# LinSen_beta.net
KiCad netlist of a schematic drawn in EAGLE
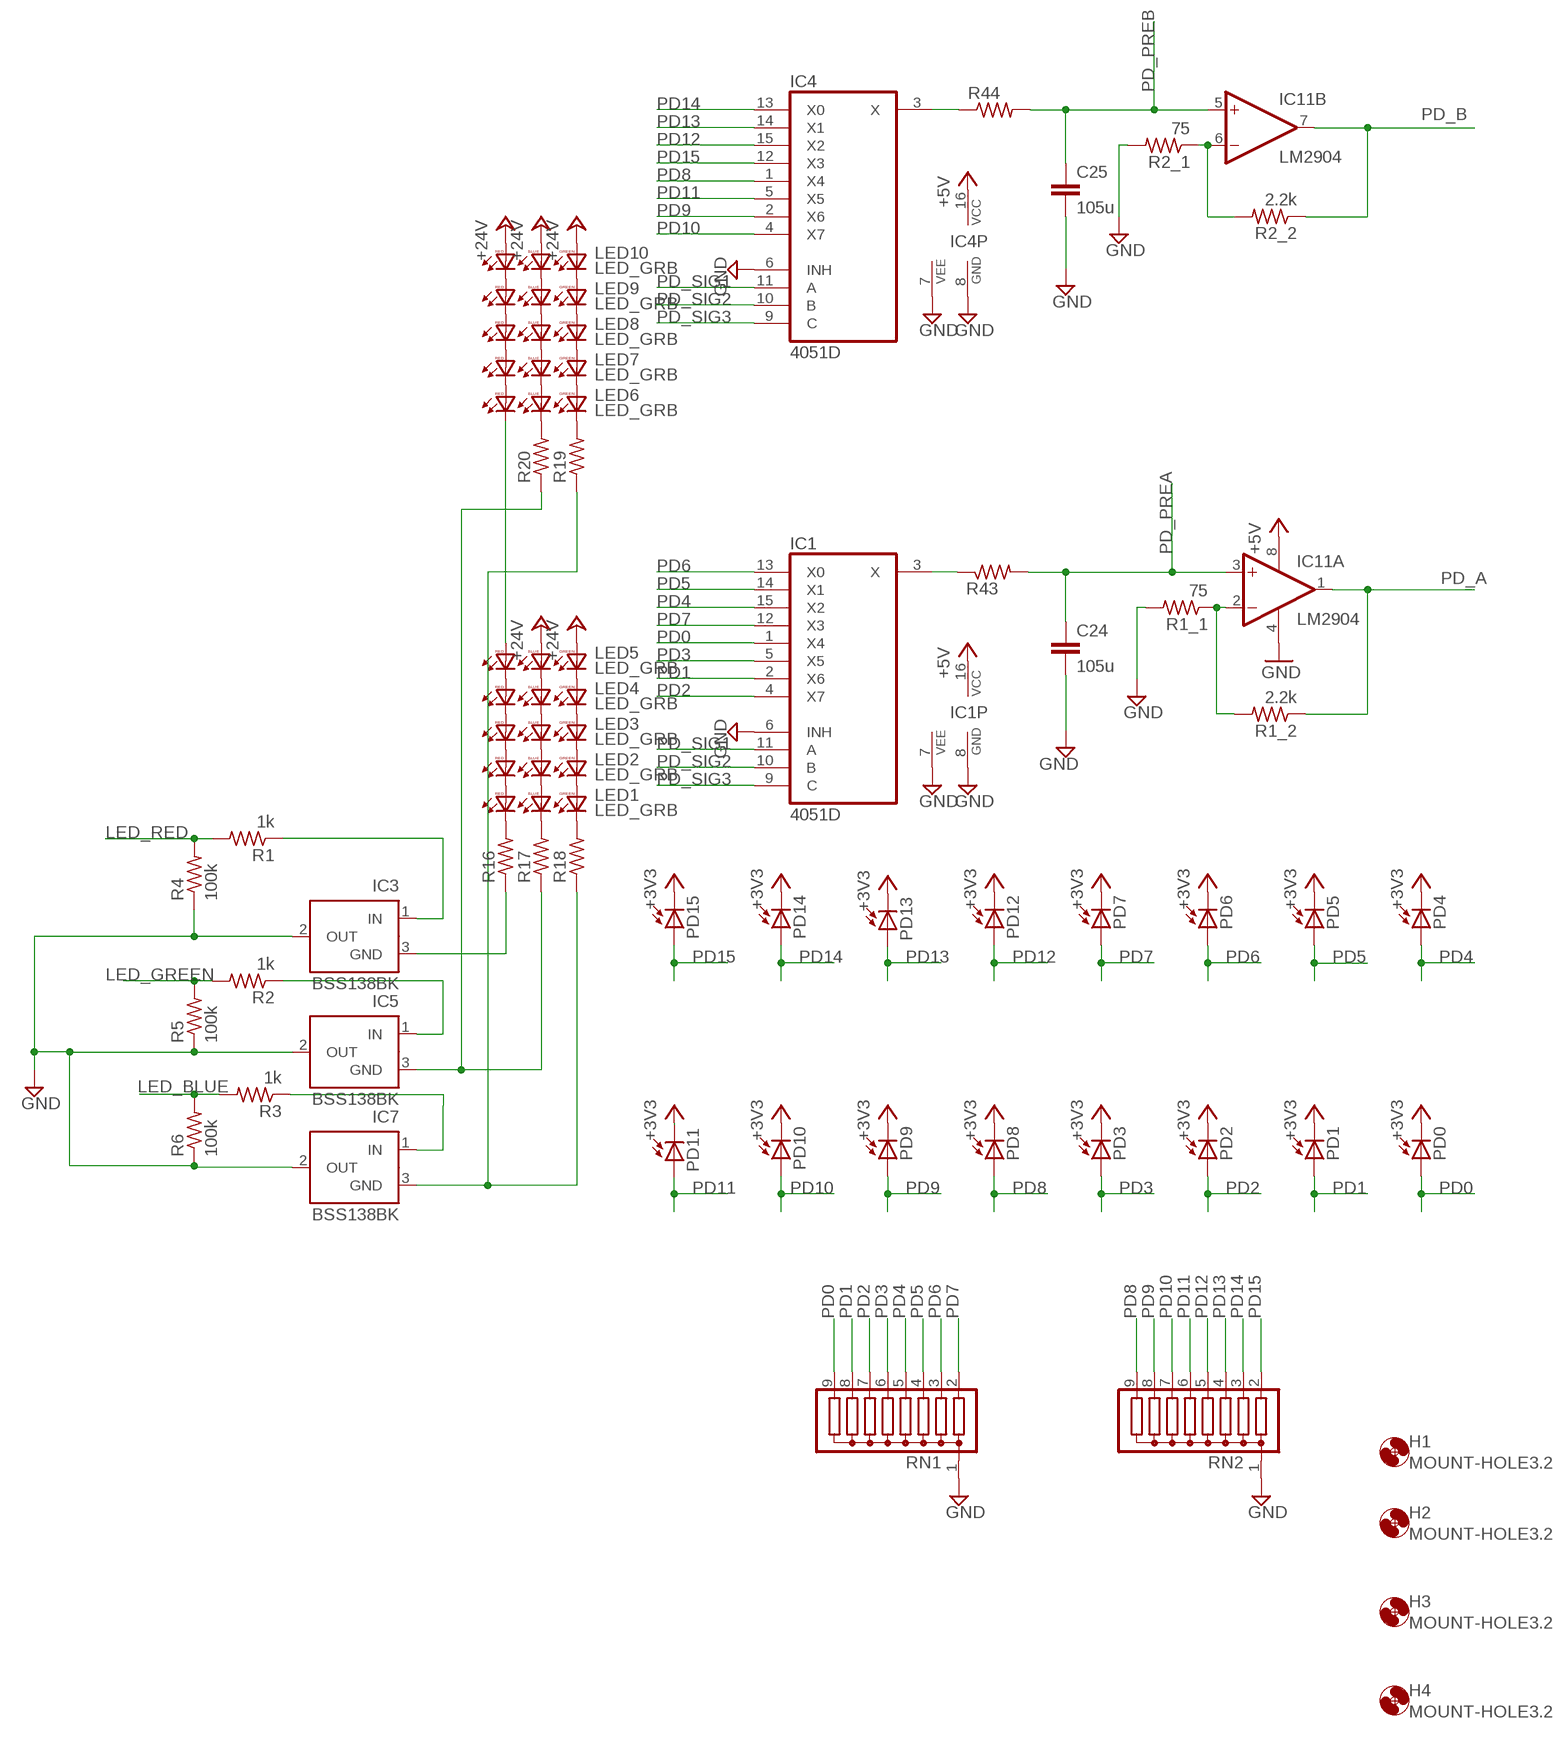
[diagram p0: schematic, sheet 1]
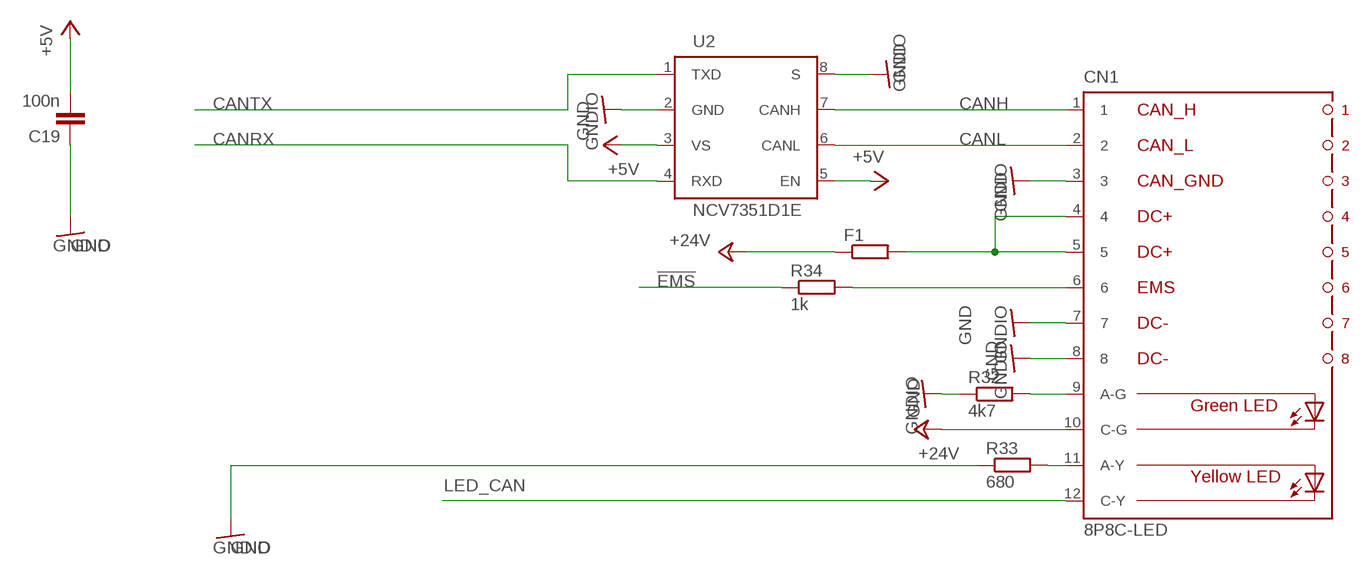
[diagram p1: schematic, sheet 2]
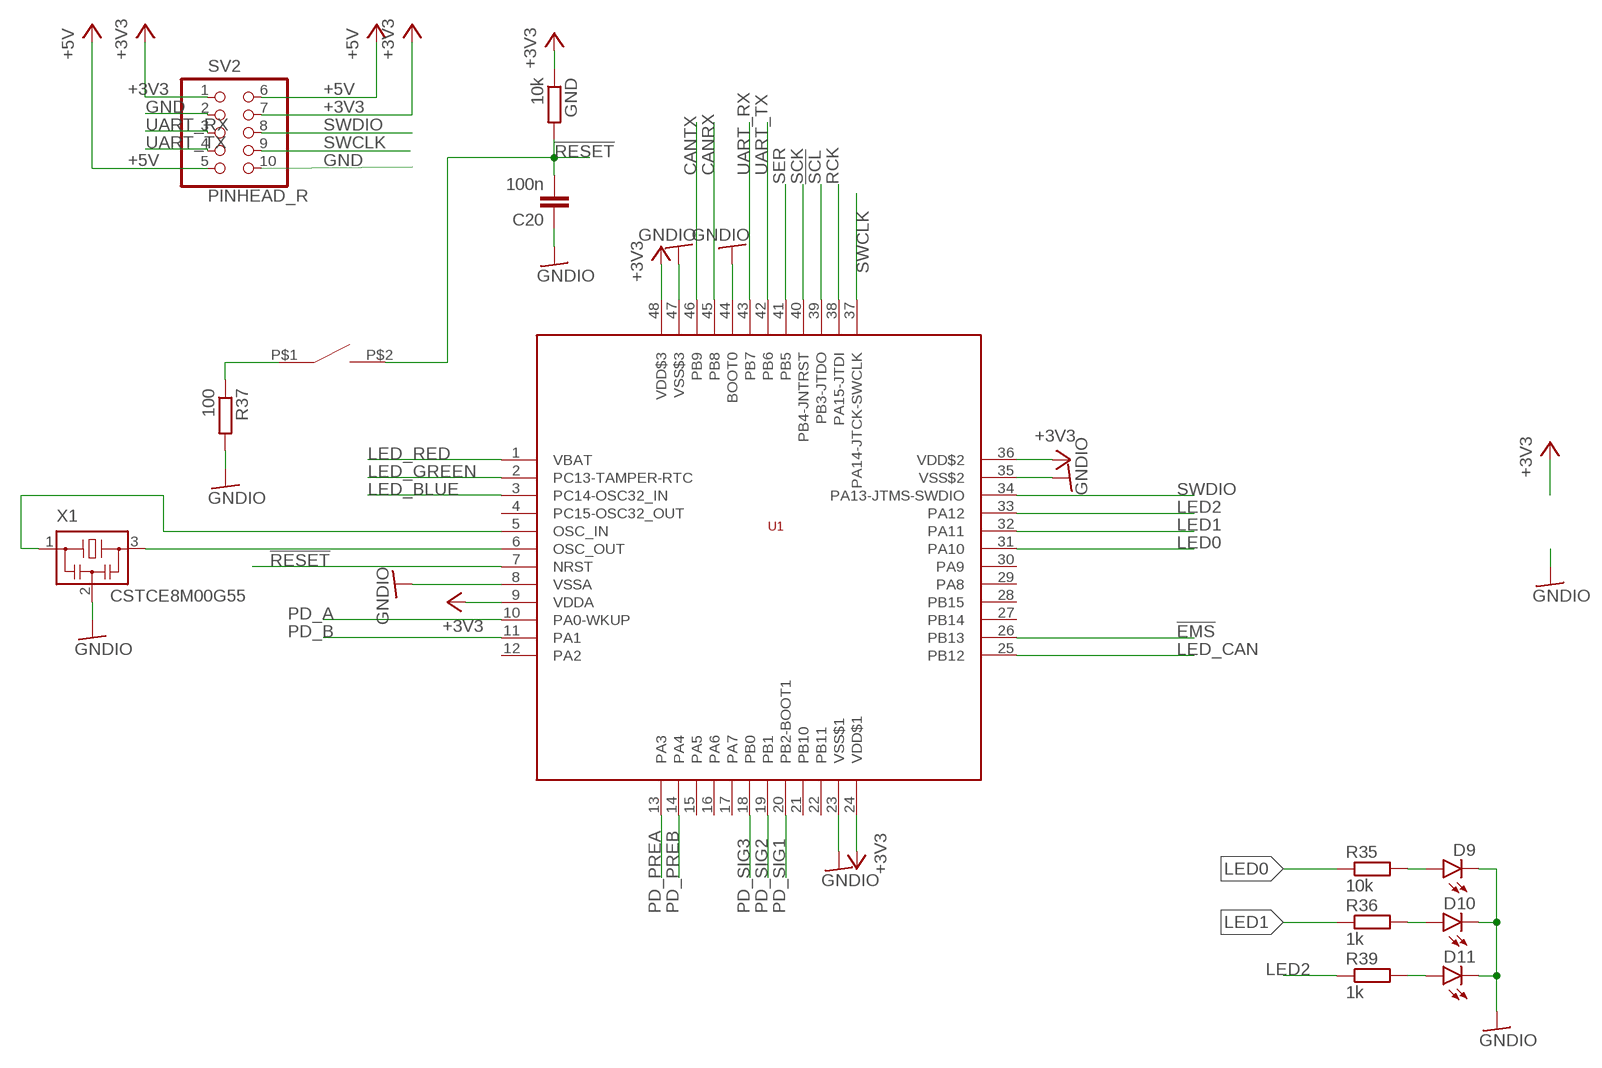
[diagram p2: schematic, sheet 3]
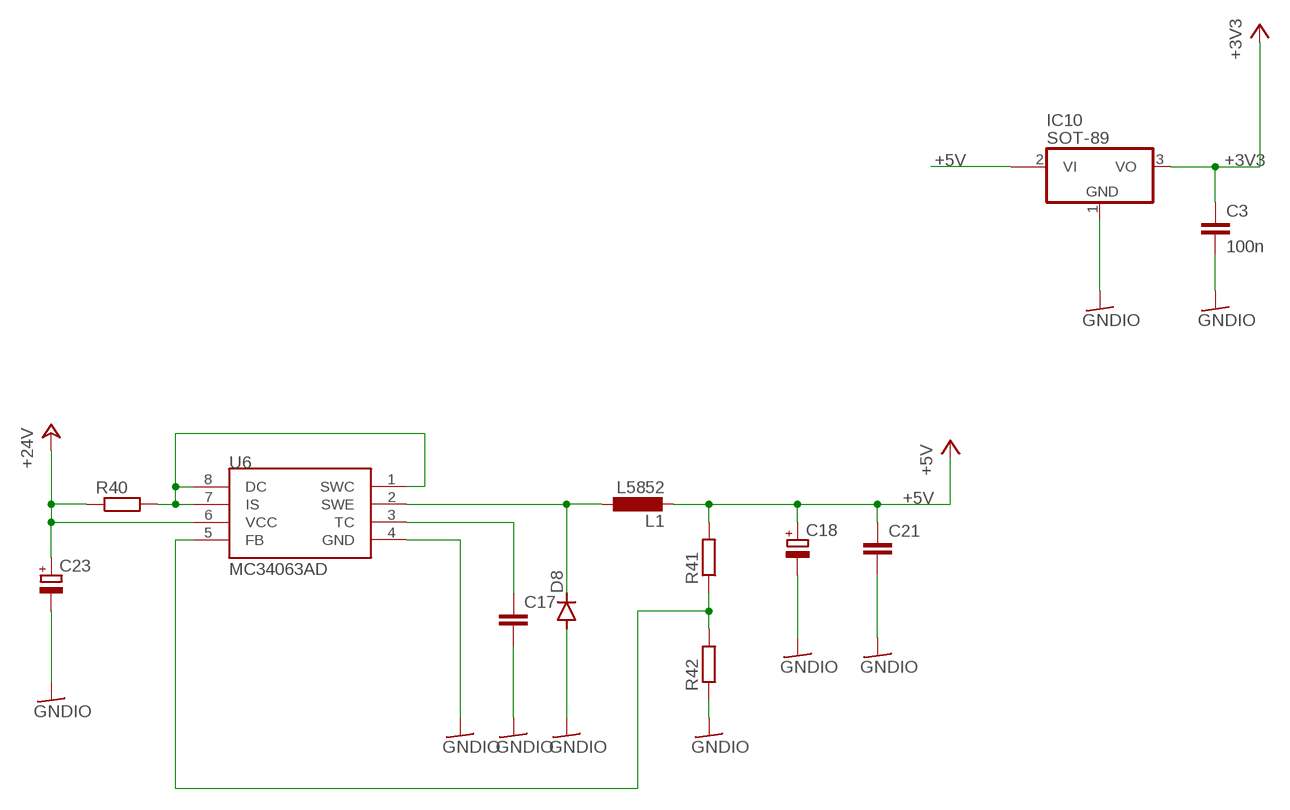
[diagram p3: schematic, sheet 4]
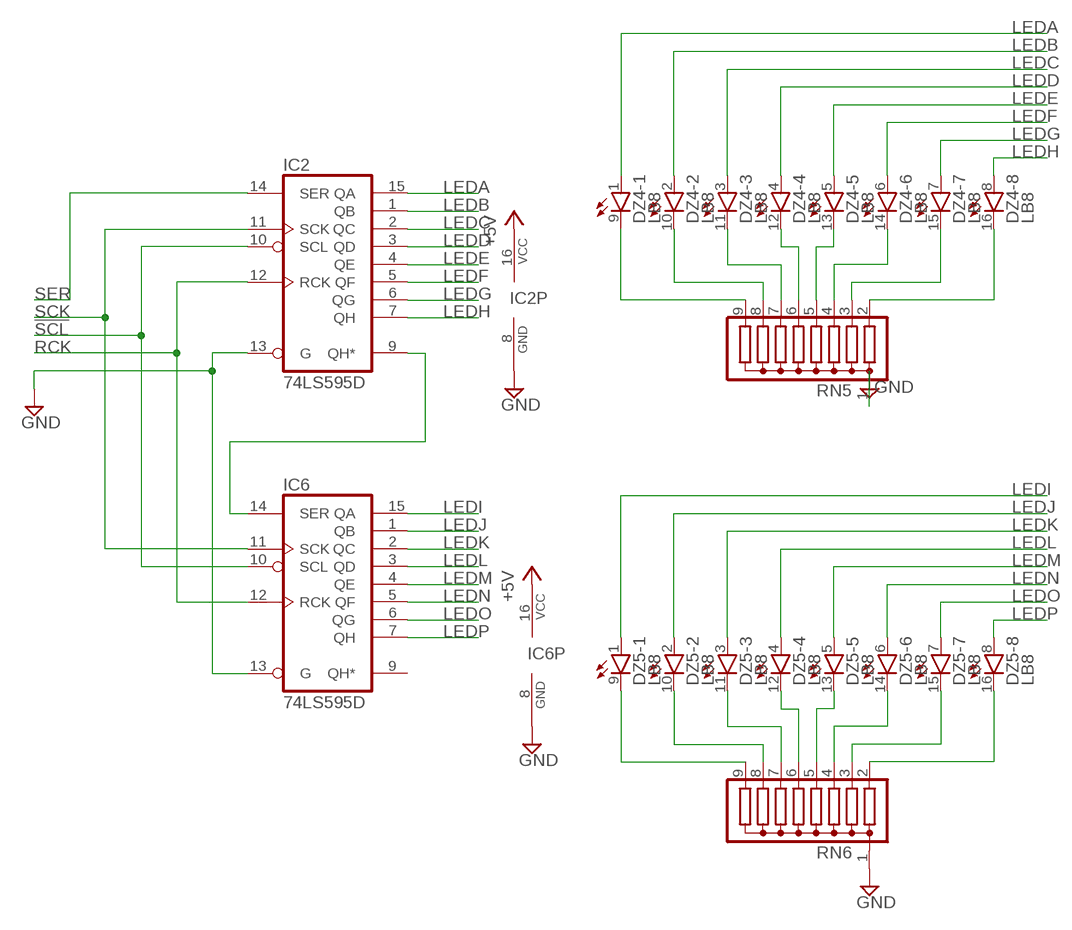
[diagram p4: schematic, sheet 5]

(export (version "E")
  (design (tool "Eeschema 10.0.6"))
  (components
    (comp (ref "DZ4")
      (value "LB8")
      (footprint "eagle-import:LB8")
      (libsource (lib "eagle-import") (part "LB8"))
    )
    (comp (ref "DZ5")
      (value "LB8")
      (footprint "eagle-import:LB8")
      (libsource (lib "eagle-import") (part "LB8"))
    )
    (comp (ref "IC2")
      (value "74LS595D")
      (footprint "eagle-import:SO16")
      (libsource (lib "eagle-import") (part "74595DLS"))
    )
    (comp (ref "IC6")
      (value "74LS595D")
      (footprint "eagle-import:SO16")
      (libsource (lib "eagle-import") (part "74595DLS"))
    )
    (comp (ref "RN5")
      (value "G08R")
      (footprint "eagle-import:SIL9")
      (libsource (lib "eagle-import") (part "G08R"))
    )
    (comp (ref "RN6")
      (value "G08R")
      (footprint "eagle-import:SIL9")
      (libsource (lib "eagle-import") (part "G08R"))
    )
    (comp (ref "C20")
      (value "100n")
      (footprint "eagle-import:C0603")
      (libsource (lib "eagle-import") (part "C-EUC0603"))
    )
    (comp (ref "D9")
      (value "LEDCHIPLED_0805")
      (footprint "eagle-import:CHIPLED_0805")
      (libsource (lib "eagle-import") (part "LEDCHIPLED_0805"))
    )
    (comp (ref "D10")
      (value "LEDCHIPLED_0805")
      (footprint "eagle-import:CHIPLED_0805")
      (libsource (lib "eagle-import") (part "LEDCHIPLED_0805"))
    )
    (comp (ref "D11")
      (value "LEDCHIPLED_0805")
      (footprint "eagle-import:CHIPLED_0805")
      (libsource (lib "eagle-import") (part "LEDCHIPLED_0805"))
    )
    (comp (ref "GND")
      (value "10k")
      (footprint "eagle-import:R0603")
      (libsource (lib "eagle-import") (part "R-EU_R0603"))
    )
    (comp (ref "R35")
      (value "10k")
      (footprint "eagle-import:R0603")
      (libsource (lib "eagle-import") (part "R-EU_R0603"))
    )
    (comp (ref "R36")
      (value "1k")
      (footprint "eagle-import:R0603")
      (libsource (lib "eagle-import") (part "R-EU_R0603"))
    )
    (comp (ref "R37")
      (value "100")
      (footprint "eagle-import:R0603")
      (libsource (lib "eagle-import") (part "R-EU_R0603"))
    )
    (comp (ref "R39")
      (value "1k")
      (footprint "eagle-import:R0603")
      (libsource (lib "eagle-import") (part "R-EU_R0603"))
    )
    (comp (ref "SV2")
      (value "PINHEAD_R")
      (footprint "eagle-import:PINHEDA_R")
      (libsource (lib "eagle-import") (part "PINHEAD_R"))
    )
    (comp (ref "SW1")
      (value "SWITCH_TACTILETOP")
      (footprint "eagle-import:SWITCH_TACTILE_3X6")
      (libsource (lib "eagle-import") (part "SWITCH_TACTILETOP"))
    )
    (comp (ref "U1")
      (value "STM32F103C8")
      (footprint "eagle-import:LQFP48")
      (libsource (lib "eagle-import") (part "STM32F103C8"))
    )
    (comp (ref "X1")
      (value "CSTCE8M00G55")
      (footprint "eagle-import:CSTCE8M00G55")
      (libsource (lib "eagle-import") (part "CSTCE8M00G55"))
    )
    (comp (ref "C24")
      (value "105u")
      (footprint "eagle-import:C0805")
      (libsource (lib "eagle-import") (part "rcl_334_C-EUC0805"))
    )
    (comp (ref "C25")
      (value "105u")
      (footprint "eagle-import:C0805")
      (libsource (lib "eagle-import") (part "rcl_334_C-EUC0805"))
    )
    (comp (ref "H1")
      (value "MOUNT-HOLE3.2")
      (footprint "eagle-import:3,2")
      (libsource (lib "eagle-import") (part "MOUNT-HOLE3.2"))
    )
    (comp (ref "H2")
      (value "MOUNT-HOLE3.2")
      (footprint "eagle-import:3,2")
      (libsource (lib "eagle-import") (part "MOUNT-HOLE3.2"))
    )
    (comp (ref "H3")
      (value "MOUNT-HOLE3.2")
      (footprint "eagle-import:3,2")
      (libsource (lib "eagle-import") (part "MOUNT-HOLE3.2"))
    )
    (comp (ref "H4")
      (value "MOUNT-HOLE3.2")
      (footprint "eagle-import:3,2")
      (libsource (lib "eagle-import") (part "MOUNT-HOLE3.2"))
    )
    (comp (ref "IC1")
      (value "4051D")
      (footprint "eagle-import:SO16")
      (fields (field (name "SPICEPREFIX") "X"))
      (libsource (lib "eagle-import") (part "4051D"))
    )
    (comp (ref "IC3")
      (value "BSS138BK")
      (footprint "eagle-import:SOT23")
      (fields (field (name "MF") "MAXIM") (field (name "MPN") "MAX6520EUR-T"))
      (libsource (lib "eagle-import") (part "MAX6520"))
    )
    (comp (ref "IC4")
      (value "4051D")
      (footprint "eagle-import:SO16")
      (libsource (lib "eagle-import") (part "4051D"))
    )
    (comp (ref "IC5")
      (value "BSS138BK")
      (footprint "eagle-import:SOT23")
      (fields (field (name "MF") "MAXIM") (field (name "MPN") "MAX6520EUR-T"))
      (libsource (lib "eagle-import") (part "MAX6520"))
    )
    (comp (ref "IC7")
      (value "BSS138BK")
      (footprint "eagle-import:SOT23")
      (fields (field (name "MF") "MAXIM") (field (name "MPN") "MAX6520EUR-T"))
      (libsource (lib "eagle-import") (part "MAX6520"))
    )
    (comp (ref "IC11")
      (value "LM2904")
      (footprint "eagle-import:SO08")
      (libsource (lib "eagle-import") (part "LM2903D"))
    )
    (comp (ref "LED1")
      (value "LED_GRB")
      (footprint "eagle-import:LED_GRB")
      (libsource (lib "eagle-import") (part "LED_GRB"))
    )
    (comp (ref "LED2")
      (value "LED_GRB")
      (footprint "eagle-import:LED_GRB")
      (libsource (lib "eagle-import") (part "LED_GRB"))
    )
    (comp (ref "LED3")
      (value "LED_GRB")
      (footprint "eagle-import:LED_GRB")
      (libsource (lib "eagle-import") (part "LED_GRB"))
    )
    (comp (ref "LED4")
      (value "LED_GRB")
      (footprint "eagle-import:LED_GRB")
      (libsource (lib "eagle-import") (part "LED_GRB"))
    )
    (comp (ref "LED5")
      (value "LED_GRB")
      (footprint "eagle-import:LED_GRB")
      (libsource (lib "eagle-import") (part "LED_GRB"))
    )
    (comp (ref "LED6")
      (value "LED_GRB")
      (footprint "eagle-import:LED_GRB")
      (libsource (lib "eagle-import") (part "LED_GRB"))
    )
    (comp (ref "LED7")
      (value "LED_GRB")
      (footprint "eagle-import:LED_GRB")
      (libsource (lib "eagle-import") (part "LED_GRB"))
    )
    (comp (ref "LED8")
      (value "LED_GRB")
      (footprint "eagle-import:LED_GRB")
      (libsource (lib "eagle-import") (part "LED_GRB"))
    )
    (comp (ref "LED9")
      (value "LED_GRB")
      (footprint "eagle-import:LED_GRB")
      (libsource (lib "eagle-import") (part "LED_GRB"))
    )
    (comp (ref "LED10")
      (value "LED_GRB")
      (footprint "eagle-import:LED_GRB")
      (libsource (lib "eagle-import") (part "LED_GRB"))
    )
    (comp (ref "PD0")
      (value "PDSFH229")
      (footprint "eagle-import:SFH229")
      (libsource (lib "eagle-import") (part "PDSFH229"))
    )
    (comp (ref "PD1")
      (value "PDSFH229")
      (footprint "eagle-import:SFH229")
      (libsource (lib "eagle-import") (part "PDSFH229"))
    )
    (comp (ref "PD2")
      (value "PDSFH229")
      (footprint "eagle-import:SFH229")
      (libsource (lib "eagle-import") (part "PDSFH229"))
    )
    (comp (ref "PD3")
      (value "PDSFH229")
      (footprint "eagle-import:SFH229")
      (libsource (lib "eagle-import") (part "PDSFH229"))
    )
    (comp (ref "PD4")
      (value "PDSFH229")
      (footprint "eagle-import:SFH229")
      (libsource (lib "eagle-import") (part "PDSFH229"))
    )
    (comp (ref "PD5")
      (value "PDSFH229")
      (footprint "eagle-import:SFH229")
      (libsource (lib "eagle-import") (part "PDSFH229"))
    )
    (comp (ref "PD6")
      (value "PDSFH229")
      (footprint "eagle-import:SFH229")
      (libsource (lib "eagle-import") (part "PDSFH229"))
    )
    (comp (ref "PD7")
      (value "PDSFH229")
      (footprint "eagle-import:SFH229")
      (libsource (lib "eagle-import") (part "PDSFH229"))
    )
    (comp (ref "PD8")
      (value "PDSFH229")
      (footprint "eagle-import:SFH229")
      (libsource (lib "eagle-import") (part "PDSFH229"))
    )
    (comp (ref "PD9")
      (value "PDSFH229")
      (footprint "eagle-import:SFH229")
      (libsource (lib "eagle-import") (part "PDSFH229"))
    )
    (comp (ref "PD10")
      (value "PDSFH229")
      (footprint "eagle-import:SFH229")
      (libsource (lib "eagle-import") (part "PDSFH229"))
    )
    (comp (ref "PD11")
      (value "PDSFH229")
      (footprint "eagle-import:SFH229")
      (libsource (lib "eagle-import") (part "PDSFH229"))
    )
    (comp (ref "PD12")
      (value "PDSFH229")
      (footprint "eagle-import:SFH229")
      (libsource (lib "eagle-import") (part "PDSFH229"))
    )
    (comp (ref "PD13")
      (value "PDSFH229")
      (footprint "eagle-import:SFH229")
      (libsource (lib "eagle-import") (part "PDSFH229"))
    )
    (comp (ref "PD14")
      (value "PDSFH229")
      (footprint "eagle-import:SFH229")
      (libsource (lib "eagle-import") (part "PDSFH229"))
    )
    (comp (ref "PD15")
      (value "PDSFH229")
      (footprint "eagle-import:SFH229")
      (libsource (lib "eagle-import") (part "PDSFH229"))
    )
    (comp (ref "R1")
      (value "1k")
      (footprint "eagle-import:R0603")
      (libsource (lib "eagle-import") (part "R-US_R0603"))
    )
    (comp (ref "R1_1")
      (value "75")
      (footprint "eagle-import:R0603")
      (libsource (lib "eagle-import") (part "R-US_R0603"))
    )
    (comp (ref "R1_2")
      (value "2.2k")
      (footprint "eagle-import:R0603")
      (libsource (lib "eagle-import") (part "R-US_R0603"))
    )
    (comp (ref "R2")
      (value "1k")
      (footprint "eagle-import:R0603")
      (libsource (lib "eagle-import") (part "R-US_R0603"))
    )
    (comp (ref "R2_1")
      (value "75")
      (footprint "eagle-import:R0603")
      (libsource (lib "eagle-import") (part "R-US_R0603"))
    )
    (comp (ref "R2_2")
      (value "2.2k")
      (footprint "eagle-import:R0603")
      (libsource (lib "eagle-import") (part "R-US_R0603"))
    )
    (comp (ref "R3")
      (value "1k")
      (footprint "eagle-import:R0603")
      (libsource (lib "eagle-import") (part "R-US_R0603"))
    )
    (comp (ref "R4")
      (value "100k")
      (footprint "eagle-import:R0603")
      (libsource (lib "eagle-import") (part "R-US_R0603"))
    )
    (comp (ref "R5")
      (value "100k")
      (footprint "eagle-import:R0603")
      (libsource (lib "eagle-import") (part "R-US_R0603"))
    )
    (comp (ref "R6")
      (value "100k")
      (footprint "eagle-import:R0603")
      (libsource (lib "eagle-import") (part "R-US_R0603"))
    )
    (comp (ref "R16")
      (value "R-US_R0603")
      (footprint "eagle-import:R0603")
      (libsource (lib "eagle-import") (part "R-US_R0603"))
    )
    (comp (ref "R17")
      (value "R-US_R0603")
      (footprint "eagle-import:R0603")
      (libsource (lib "eagle-import") (part "R-US_R0603"))
    )
    (comp (ref "R18")
      (value "R-US_R0603")
      (footprint "eagle-import:R0603")
      (libsource (lib "eagle-import") (part "R-US_R0603"))
    )
    (comp (ref "R19")
      (value "R-US_R0603")
      (footprint "eagle-import:R0603")
      (libsource (lib "eagle-import") (part "R-US_R0603"))
    )
    (comp (ref "R20")
      (value "R-US_R0603")
      (footprint "eagle-import:R0603")
      (libsource (lib "eagle-import") (part "R-US_R0603"))
    )
    (comp (ref "R43")
      (value "R-US_R0603")
      (footprint "eagle-import:R0603")
      (libsource (lib "eagle-import") (part "R-US_R0603"))
    )
    (comp (ref "R44")
      (value "R-US_R0603")
      (footprint "eagle-import:R0603")
      (libsource (lib "eagle-import") (part "R-US_R0603"))
    )
    (comp (ref "RN1")
      (value "G08R")
      (footprint "eagle-import:SIL9")
      (libsource (lib "eagle-import") (part "G08R"))
    )
    (comp (ref "RN2")
      (value "G08R")
      (footprint "eagle-import:SIL9")
      (libsource (lib "eagle-import") (part "G08R"))
    )
    (comp (ref "C19")
      (value "100n")
      (footprint "eagle-import:C0603")
      (libsource (lib "eagle-import") (part "C-EUC0603"))
    )
    (comp (ref "CN1")
      (value "8P8C-LED")
      (footprint "eagle-import:8P8C-LED")
      (libsource (lib "eagle-import") (part "8P8C-LED"))
    )
    (comp (ref "F1")
      (value "R-EU_R1206")
      (footprint "eagle-import:R1206")
      (libsource (lib "eagle-import") (part "rcl_334_R-EU_R1206"))
    )
    (comp (ref "R32")
      (value "4k7")
      (footprint "eagle-import:R0603")
      (libsource (lib "eagle-import") (part "rcl_334_R-EU_R0603"))
    )
    (comp (ref "R33")
      (value "680")
      (footprint "eagle-import:R0603")
      (libsource (lib "eagle-import") (part "rcl_334_R-EU_R0603"))
    )
    (comp (ref "R34")
      (value "1k")
      (footprint "eagle-import:R0603")
      (libsource (lib "eagle-import") (part "rcl_334_R-EU_R0603"))
    )
    (comp (ref "U2")
      (value "NCV7351D1E")
      (footprint "eagle-import:SO08")
      (libsource (lib "eagle-import") (part "NCV7351D1E"))
    )
    (comp (ref "C3")
      (value "100n")
      (footprint "eagle-import:C0603")
      (libsource (lib "eagle-import") (part "C-EUC0603"))
    )
    (comp (ref "C17")
      (value "C-EUC0603")
      (footprint "eagle-import:C0603")
      (libsource (lib "eagle-import") (part "rcl_334_C-EUC0603"))
    )
    (comp (ref "C18")
      (value "CPOL-EUE2-5")
      (footprint "eagle-import:E2-5")
      (libsource (lib "eagle-import") (part "CPOL-EUE2-5"))
    )
    (comp (ref "C21")
      (value "C-EUC0603")
      (footprint "eagle-import:C0603")
      (libsource (lib "eagle-import") (part "C-EUC0603"))
    )
    (comp (ref "C23")
      (value "CPOL-EUE2-5")
      (footprint "eagle-import:E2-5")
      (libsource (lib "eagle-import") (part "CPOL-EUE2-5"))
    )
    (comp (ref "D8")
      (value "DIODE-SOD123")
      (footprint "eagle-import:SOD123")
      (libsource (lib "eagle-import") (part "DIODE-SOD123"))
    )
    (comp (ref "IC10")
      (value "SOT-89")
      (footprint "eagle-import:SOT89")
      (libsource (lib "eagle-import") (part "MCP1703MB12"))
    )
    (comp (ref "L1")
      (value "L5852")
      (footprint "eagle-import:L5852")
      (libsource (lib "eagle-import") (part "L5852"))
    )
    (comp (ref "R40")
      (value "R-EU_R1206")
      (footprint "eagle-import:R1206")
      (libsource (lib "eagle-import") (part "rcl_334_R-EU_R1206"))
    )
    (comp (ref "R41")
      (value "R-EU_R0603")
      (footprint "eagle-import:R0603")
      (libsource (lib "eagle-import") (part "rcl_334_R-EU_R0603"))
    )
    (comp (ref "R42")
      (value "R-EU_R0603")
      (footprint "eagle-import:R0603")
      (libsource (lib "eagle-import") (part "rcl_334_R-EU_R0603"))
    )
    (comp (ref "U6")
      (value "MC34063AD")
      (footprint "eagle-import:SOIC8")
      (libsource (lib "eagle-import") (part "MC34063AD"))
    )
  )
  (nets
    (net (code "1") (name "+3V3") (class "Default")
      (node (ref "C3") (pin "1") (pinfunction "1_1") (pintype "passive"))
      (node (ref "GND") (pin "1") (pinfunction "1_1") (pintype "passive"))
      (node (ref "IC10") (pin "3") (pinfunction "VO_3") (pintype "passive"))
      (node (ref "PD0") (pin "K") (pinfunction "C_K") (pintype "passive"))
      (node (ref "PD1") (pin "K") (pinfunction "C_K") (pintype "passive"))
      (node (ref "PD10") (pin "K") (pinfunction "C_K") (pintype "passive"))
      (node (ref "PD11") (pin "K") (pinfunction "C_K") (pintype "passive"))
      (node (ref "PD12") (pin "K") (pinfunction "C_K") (pintype "passive"))
      (node (ref "PD13") (pin "K") (pinfunction "C_K") (pintype "passive"))
      (node (ref "PD14") (pin "K") (pinfunction "C_K") (pintype "passive"))
      (node (ref "PD15") (pin "K") (pinfunction "C_K") (pintype "passive"))
      (node (ref "PD2") (pin "K") (pinfunction "C_K") (pintype "passive"))
      (node (ref "PD3") (pin "K") (pinfunction "C_K") (pintype "passive"))
      (node (ref "PD4") (pin "K") (pinfunction "C_K") (pintype "passive"))
      (node (ref "PD5") (pin "K") (pinfunction "C_K") (pintype "passive"))
      (node (ref "PD6") (pin "K") (pinfunction "C_K") (pintype "passive"))
      (node (ref "PD7") (pin "K") (pinfunction "C_K") (pintype "passive"))
      (node (ref "PD8") (pin "K") (pinfunction "C_K") (pintype "passive"))
      (node (ref "PD9") (pin "K") (pinfunction "C_K") (pintype "passive"))
      (node (ref "SV2") (pin "1") (pinfunction "1_1") (pintype "passive"))
      (node (ref "SV2") (pin "7") (pinfunction "7_7") (pintype "passive"))
      (node (ref "U1") (pin "24") (pinfunction "VDD$1_24") (pintype "passive"))
      (node (ref "U1") (pin "36") (pinfunction "VDD$2_36") (pintype "passive"))
      (node (ref "U1") (pin "48") (pinfunction "VDD$3_48") (pintype "passive"))
      (node (ref "U1") (pin "9") (pinfunction "VDDA_9") (pintype "bidirectional"))
    )
    (net (code "2") (name "+5V") (class "Default")
      (node (ref "C18") (pin "+") (pinfunction "+_+") (pintype "passive"))
      (node (ref "C19") (pin "2") (pinfunction "2_2") (pintype "passive"))
      (node (ref "C21") (pin "1") (pinfunction "1_1") (pintype "passive"))
      (node (ref "IC1") (pin "16") (pinfunction "VCC_16") (pintype "power_in"))
      (node (ref "IC10") (pin "2@1") (pinfunction "VI1_2@1") (pintype "input"))
      (node (ref "IC11") (pin "8") (pinfunction "V+_8") (pintype "power_in"))
      (node (ref "IC2") (pin "16") (pinfunction "VCC_16") (pintype "power_in"))
      (node (ref "IC4") (pin "16") (pinfunction "VCC_16") (pintype "power_in"))
      (node (ref "IC6") (pin "16") (pinfunction "VCC_16") (pintype "power_in"))
      (node (ref "L1") (pin "P$2") (pinfunction "2_P$2") (pintype "passive"))
      (node (ref "R41") (pin "2") (pinfunction "2_2") (pintype "passive"))
      (node (ref "SV2") (pin "5") (pinfunction "5_5") (pintype "passive"))
      (node (ref "SV2") (pin "6") (pinfunction "6_6") (pintype "passive"))
      (node (ref "U2") (pin "3") (pinfunction "VS_3") (pintype "power_in"))
      (node (ref "U2") (pin "5") (pinfunction "EN_5") (pintype "input"))
    )
    (net (code "3") (name "+24V") (class "Default")
      (node (ref "C23") (pin "+") (pinfunction "+_+") (pintype "passive"))
      (node (ref "CN1") (pin "10") (pinfunction "C-G_10") (pintype "passive"))
      (node (ref "F1") (pin "1") (pinfunction "1_1") (pintype "passive"))
      (node (ref "LED10") (pin "BA") (pinfunction "BA_BA") (pintype "passive"))
      (node (ref "LED10") (pin "GA") (pinfunction "GA_GA") (pintype "passive"))
      (node (ref "LED10") (pin "RA") (pinfunction "RA_RA") (pintype "passive"))
      (node (ref "LED5") (pin "BA") (pinfunction "BA_BA") (pintype "passive"))
      (node (ref "LED5") (pin "GA") (pinfunction "GA_GA") (pintype "passive"))
      (node (ref "R40") (pin "1") (pinfunction "1_1") (pintype "passive"))
      (node (ref "U6") (pin "6") (pinfunction "VCC_6") (pintype "passive"))
    )
    (net (code "4") (name "CANH") (class "Default")
      (node (ref "CN1") (pin "1") (pinfunction "1_1") (pintype "input"))
      (node (ref "U2") (pin "7") (pinfunction "CANH_7") (pintype "output"))
    )
    (net (code "5") (name "CANL") (class "Default")
      (node (ref "CN1") (pin "2") (pinfunction "2_2") (pintype "input"))
      (node (ref "U2") (pin "6") (pinfunction "CANL_6") (pintype "output"))
    )
    (net (code "6") (name "CANRX") (class "Default")
      (node (ref "U1") (pin "45") (pinfunction "PB8_45") (pintype "bidirectional"))
      (node (ref "U2") (pin "4") (pinfunction "RXD_4") (pintype "output"))
    )
    (net (code "7") (name "CANTX") (class "Default")
      (node (ref "U1") (pin "46") (pinfunction "PB9_46") (pintype "bidirectional"))
      (node (ref "U2") (pin "1") (pinfunction "TXD_1") (pintype "input"))
    )
    (net (code "8") (name "GND") (class "Default")
      (node (ref "C17") (pin "2") (pinfunction "2_2") (pintype "passive"))
      (node (ref "C18") (pin "-") (pinfunction "-_-") (pintype "passive"))
      (node (ref "C19") (pin "1") (pinfunction "1_1") (pintype "passive"))
      (node (ref "C20") (pin "1") (pinfunction "1_1") (pintype "passive"))
      (node (ref "C21") (pin "2") (pinfunction "2_2") (pintype "passive"))
      (node (ref "C23") (pin "-") (pinfunction "-_-") (pintype "passive"))
      (node (ref "C24") (pin "2") (pinfunction "2_2") (pintype "passive"))
      (node (ref "C25") (pin "2") (pinfunction "2_2") (pintype "passive"))
      (node (ref "C3") (pin "2") (pinfunction "2_2") (pintype "passive"))
      (node (ref "CN1") (pin "3") (pinfunction "3_3") (pintype "input"))
      (node (ref "CN1") (pin "7") (pinfunction "7_7") (pintype "input"))
      (node (ref "CN1") (pin "8") (pinfunction "8_8") (pintype "input"))
      (node (ref "D10") (pin "C") (pinfunction "C_C") (pintype "passive"))
      (node (ref "D11") (pin "C") (pinfunction "C_C") (pintype "passive"))
      (node (ref "D8") (pin "A") (pinfunction "A_A") (pintype "passive"))
      (node (ref "D9") (pin "C") (pinfunction "C_C") (pintype "passive"))
      (node (ref "IC1") (pin "6") (pinfunction "INH_6") (pintype "input"))
      (node (ref "IC1") (pin "7") (pinfunction "VEE_7") (pintype "power_in"))
      (node (ref "IC1") (pin "8") (pinfunction "GND_8") (pintype "power_in"))
      (node (ref "IC10") (pin "1") (pinfunction "GND_1") (pintype "passive"))
      (node (ref "IC11") (pin "4") (pinfunction "V-_4") (pintype "power_in"))
      (node (ref "IC2") (pin "13") (pinfunction "G_13") (pintype "input"))
      (node (ref "IC2") (pin "8") (pinfunction "GND_8") (pintype "power_in"))
      (node (ref "IC3") (pin "2") (pinfunction "OUT_2") (pintype "output"))
      (node (ref "IC4") (pin "6") (pinfunction "INH_6") (pintype "input"))
      (node (ref "IC4") (pin "7") (pinfunction "VEE_7") (pintype "power_in"))
      (node (ref "IC4") (pin "8") (pinfunction "GND_8") (pintype "power_in"))
      (node (ref "IC5") (pin "2") (pinfunction "OUT_2") (pintype "output"))
      (node (ref "IC6") (pin "13") (pinfunction "G_13") (pintype "input"))
      (node (ref "IC6") (pin "8") (pinfunction "GND_8") (pintype "power_in"))
      (node (ref "IC7") (pin "2") (pinfunction "OUT_2") (pintype "output"))
      (node (ref "R1_1") (pin "2") (pinfunction "2_2") (pintype "passive"))
      (node (ref "R2_1") (pin "2") (pinfunction "2_2") (pintype "passive"))
      (node (ref "R32") (pin "1") (pinfunction "1_1") (pintype "passive"))
      (node (ref "R33") (pin "1") (pinfunction "1_1") (pintype "passive"))
      (node (ref "R37") (pin "2") (pinfunction "2_2") (pintype "passive"))
      (node (ref "R4") (pin "1") (pinfunction "1_1") (pintype "passive"))
      (node (ref "R42") (pin "1") (pinfunction "1_1") (pintype "passive"))
      (node (ref "R5") (pin "1") (pinfunction "1_1") (pintype "passive"))
      (node (ref "R6") (pin "1") (pinfunction "1_1") (pintype "passive"))
      (node (ref "RN1") (pin "1") (pinfunction "1_1") (pintype "passive"))
      (node (ref "RN2") (pin "1") (pinfunction "1_1") (pintype "passive"))
      (node (ref "RN5") (pin "1") (pinfunction "1_1") (pintype "passive"))
      (node (ref "RN6") (pin "1") (pinfunction "1_1") (pintype "passive"))
      (node (ref "SV2") (pin "10") (pinfunction "10_10") (pintype "passive"))
      (node (ref "SV2") (pin "2") (pinfunction "2_2") (pintype "passive"))
      (node (ref "U1") (pin "23") (pinfunction "VSS$1_23") (pintype "passive"))
      (node (ref "U1") (pin "35") (pinfunction "VSS$2_35") (pintype "passive"))
      (node (ref "U1") (pin "44") (pinfunction "BOOT0_44") (pintype "input"))
      (node (ref "U1") (pin "47") (pinfunction "VSS$3_47") (pintype "passive"))
      (node (ref "U1") (pin "8") (pinfunction "VSSA_8") (pintype "bidirectional"))
      (node (ref "U2") (pin "2") (pinfunction "GND_2") (pintype "power_in"))
      (node (ref "U2") (pin "8") (pinfunction "S_8") (pintype "input"))
      (node (ref "U6") (pin "4") (pinfunction "GND_4") (pintype "passive"))
      (node (ref "X1") (pin "2") (pinfunction "2_2") (pintype "passive"))
    )
    (net (code "9") (name "LED0") (class "Default")
      (node (ref "R35") (pin "1") (pinfunction "1_1") (pintype "passive"))
      (node (ref "U1") (pin "31") (pinfunction "PA10_31") (pintype "bidirectional"))
    )
    (net (code "10") (name "LED1") (class "Default")
      (node (ref "R36") (pin "1") (pinfunction "1_1") (pintype "passive"))
      (node (ref "U1") (pin "32") (pinfunction "PA11_32") (pintype "bidirectional"))
    )
    (net (code "11") (name "LED2") (class "Default")
      (node (ref "R39") (pin "1") (pinfunction "1_1") (pintype "passive"))
      (node (ref "U1") (pin "33") (pinfunction "PA12_33") (pintype "bidirectional"))
    )
    (net (code "12") (name "LEDA") (class "Default")
      (node (ref "DZ4") (pin "1") (pinfunction "A_1") (pintype "passive"))
      (node (ref "IC2") (pin "15") (pinfunction "QA_15") (pintype "tri_state"))
    )
    (net (code "13") (name "LEDB") (class "Default")
      (node (ref "DZ4") (pin "2") (pinfunction "A_2") (pintype "passive"))
      (node (ref "IC2") (pin "1") (pinfunction "QB_1") (pintype "tri_state"))
    )
    (net (code "14") (name "LEDC") (class "Default")
      (node (ref "DZ4") (pin "3") (pinfunction "A_3") (pintype "passive"))
      (node (ref "IC2") (pin "2") (pinfunction "QC_2") (pintype "tri_state"))
    )
    (net (code "15") (name "LEDD") (class "Default")
      (node (ref "DZ4") (pin "4") (pinfunction "A_4") (pintype "passive"))
      (node (ref "IC2") (pin "3") (pinfunction "QD_3") (pintype "tri_state"))
    )
    (net (code "16") (name "LEDE") (class "Default")
      (node (ref "DZ4") (pin "5") (pinfunction "A_5") (pintype "passive"))
      (node (ref "IC2") (pin "4") (pinfunction "QE_4") (pintype "tri_state"))
    )
    (net (code "17") (name "LEDF") (class "Default")
      (node (ref "DZ4") (pin "6") (pinfunction "A_6") (pintype "passive"))
      (node (ref "IC2") (pin "5") (pinfunction "QF_5") (pintype "tri_state"))
    )
    (net (code "18") (name "LEDG") (class "Default")
      (node (ref "DZ4") (pin "7") (pinfunction "A_7") (pintype "passive"))
      (node (ref "IC2") (pin "6") (pinfunction "QG_6") (pintype "tri_state"))
    )
    (net (code "19") (name "LEDH") (class "Default")
      (node (ref "DZ4") (pin "8") (pinfunction "A_8") (pintype "passive"))
      (node (ref "IC2") (pin "7") (pinfunction "QH_7") (pintype "tri_state"))
    )
    (net (code "20") (name "LEDI") (class "Default")
      (node (ref "DZ5") (pin "1") (pinfunction "A_1") (pintype "passive"))
      (node (ref "IC6") (pin "15") (pinfunction "QA_15") (pintype "tri_state"))
    )
    (net (code "21") (name "LEDJ") (class "Default")
      (node (ref "DZ5") (pin "2") (pinfunction "A_2") (pintype "passive"))
      (node (ref "IC6") (pin "1") (pinfunction "QB_1") (pintype "tri_state"))
    )
    (net (code "22") (name "LEDK") (class "Default")
      (node (ref "DZ5") (pin "3") (pinfunction "A_3") (pintype "passive"))
      (node (ref "IC6") (pin "2") (pinfunction "QC_2") (pintype "tri_state"))
    )
    (net (code "23") (name "LEDL") (class "Default")
      (node (ref "DZ5") (pin "4") (pinfunction "A_4") (pintype "passive"))
      (node (ref "IC6") (pin "3") (pinfunction "QD_3") (pintype "tri_state"))
    )
    (net (code "24") (name "LEDM") (class "Default")
      (node (ref "DZ5") (pin "5") (pinfunction "A_5") (pintype "passive"))
      (node (ref "IC6") (pin "4") (pinfunction "QE_4") (pintype "tri_state"))
    )
    (net (code "25") (name "LEDN") (class "Default")
      (node (ref "DZ5") (pin "6") (pinfunction "A_6") (pintype "passive"))
      (node (ref "IC6") (pin "5") (pinfunction "QF_5") (pintype "tri_state"))
    )
    (net (code "26") (name "LEDO") (class "Default")
      (node (ref "DZ5") (pin "7") (pinfunction "A_7") (pintype "passive"))
      (node (ref "IC6") (pin "6") (pinfunction "QG_6") (pintype "tri_state"))
    )
    (net (code "27") (name "LEDP") (class "Default")
      (node (ref "DZ5") (pin "8") (pinfunction "A_8") (pintype "passive"))
      (node (ref "IC6") (pin "7") (pinfunction "QH_7") (pintype "tri_state"))
    )
    (net (code "28") (name "LED_BLUE") (class "Default")
      (node (ref "R3") (pin "2") (pinfunction "2_2") (pintype "passive"))
      (node (ref "R6") (pin "2") (pinfunction "2_2") (pintype "passive"))
      (node (ref "U1") (pin "3") (pinfunction "PC14-OSC32_IN_3") (pintype "bidirectional"))
    )
    (net (code "29") (name "LED_CAN") (class "Default")
      (node (ref "CN1") (pin "12") (pinfunction "C-Y_12") (pintype "passive"))
      (node (ref "U1") (pin "25") (pinfunction "PB12_25") (pintype "bidirectional"))
    )
    (net (code "30") (name "LED_GREEN") (class "Default")
      (node (ref "R2") (pin "2") (pinfunction "2_2") (pintype "passive"))
      (node (ref "R5") (pin "2") (pinfunction "2_2") (pintype "passive"))
      (node (ref "U1") (pin "2") (pinfunction "PC13-TAMPER-RTC_2") (pintype "bidirectional"))
    )
    (net (code "31") (name "LED_RED") (class "Default")
      (node (ref "R1") (pin "2") (pinfunction "2_2") (pintype "passive"))
      (node (ref "R4") (pin "2") (pinfunction "2_2") (pintype "passive"))
      (node (ref "U1") (pin "1") (pinfunction "VBAT_1") (pintype "passive"))
    )
    (net (code "32") (name "Net-(CN1-A-G)") (class "Default")
      (node (ref "CN1") (pin "9") (pinfunction "A-G_9") (pintype "passive"))
      (node (ref "R32") (pin "2") (pinfunction "2_2") (pintype "passive"))
    )
    (net (code "33") (name "Net-(CN1-A-Y)") (class "Default")
      (node (ref "CN1") (pin "11") (pinfunction "A-Y_11") (pintype "passive"))
      (node (ref "R33") (pin "2") (pinfunction "2_2") (pintype "passive"))
    )
    (net (code "34") (name "Net-(CN1-Pad4)") (class "Default")
      (node (ref "CN1") (pin "4") (pinfunction "4_4") (pintype "input"))
      (node (ref "CN1") (pin "5") (pinfunction "5_5") (pintype "input"))
      (node (ref "F1") (pin "2") (pinfunction "2_2") (pintype "passive"))
    )
    (net (code "35") (name "Net-(CN1-Pad6)") (class "Default")
      (node (ref "CN1") (pin "6") (pinfunction "6_6") (pintype "input"))
      (node (ref "R34") (pin "2") (pinfunction "2_2") (pintype "passive"))
    )
    (net (code "36") (name "Net-(D9-PadA)") (class "Default")
      (node (ref "D9") (pin "A") (pinfunction "A_A") (pintype "passive"))
      (node (ref "R35") (pin "2") (pinfunction "2_2") (pintype "passive"))
    )
    (net (code "37") (name "Net-(D10-PadA)") (class "Default")
      (node (ref "D10") (pin "A") (pinfunction "A_A") (pintype "passive"))
      (node (ref "R36") (pin "2") (pinfunction "2_2") (pintype "passive"))
    )
    (net (code "38") (name "Net-(D11-PadA)") (class "Default")
      (node (ref "D11") (pin "A") (pinfunction "A_A") (pintype "passive"))
      (node (ref "R39") (pin "2") (pinfunction "2_2") (pintype "passive"))
    )
    (net (code "39") (name "Net-(DZ4A-C)") (class "Default")
      (node (ref "DZ4") (pin "9") (pinfunction "C_9") (pintype "passive"))
      (node (ref "RN5") (pin "9") (pinfunction "9_9") (pintype "passive"))
    )
    (net (code "40") (name "Net-(DZ4B-C)") (class "Default")
      (node (ref "DZ4") (pin "10") (pinfunction "C_10") (pintype "passive"))
      (node (ref "RN5") (pin "8") (pinfunction "8_8") (pintype "passive"))
    )
    (net (code "41") (name "Net-(DZ4C-C)") (class "Default")
      (node (ref "DZ4") (pin "11") (pinfunction "C_11") (pintype "passive"))
      (node (ref "RN5") (pin "7") (pinfunction "7_7") (pintype "passive"))
    )
    (net (code "42") (name "Net-(DZ4D-C)") (class "Default")
      (node (ref "DZ4") (pin "12") (pinfunction "C_12") (pintype "passive"))
      (node (ref "RN5") (pin "6") (pinfunction "6_6") (pintype "passive"))
    )
    (net (code "43") (name "Net-(DZ4E-C)") (class "Default")
      (node (ref "DZ4") (pin "13") (pinfunction "C_13") (pintype "passive"))
      (node (ref "RN5") (pin "5") (pinfunction "5_5") (pintype "passive"))
    )
    (net (code "44") (name "Net-(DZ4F-C)") (class "Default")
      (node (ref "DZ4") (pin "14") (pinfunction "C_14") (pintype "passive"))
      (node (ref "RN5") (pin "4") (pinfunction "4_4") (pintype "passive"))
    )
    (net (code "45") (name "Net-(DZ4G-C)") (class "Default")
      (node (ref "DZ4") (pin "15") (pinfunction "C_15") (pintype "passive"))
      (node (ref "RN5") (pin "3") (pinfunction "3_3") (pintype "passive"))
    )
    (net (code "46") (name "Net-(DZ4H-C)") (class "Default")
      (node (ref "DZ4") (pin "16") (pinfunction "C_16") (pintype "passive"))
      (node (ref "RN5") (pin "2") (pinfunction "2_2") (pintype "passive"))
    )
    (net (code "47") (name "Net-(DZ5A-C)") (class "Default")
      (node (ref "DZ5") (pin "9") (pinfunction "C_9") (pintype "passive"))
      (node (ref "RN6") (pin "9") (pinfunction "9_9") (pintype "passive"))
    )
    (net (code "48") (name "Net-(DZ5B-C)") (class "Default")
      (node (ref "DZ5") (pin "10") (pinfunction "C_10") (pintype "passive"))
      (node (ref "RN6") (pin "8") (pinfunction "8_8") (pintype "passive"))
    )
    (net (code "49") (name "Net-(DZ5C-C)") (class "Default")
      (node (ref "DZ5") (pin "11") (pinfunction "C_11") (pintype "passive"))
      (node (ref "RN6") (pin "7") (pinfunction "7_7") (pintype "passive"))
    )
    (net (code "50") (name "Net-(DZ5D-C)") (class "Default")
      (node (ref "DZ5") (pin "12") (pinfunction "C_12") (pintype "passive"))
      (node (ref "RN6") (pin "6") (pinfunction "6_6") (pintype "passive"))
    )
    (net (code "51") (name "Net-(DZ5E-C)") (class "Default")
      (node (ref "DZ5") (pin "13") (pinfunction "C_13") (pintype "passive"))
      (node (ref "RN6") (pin "5") (pinfunction "5_5") (pintype "passive"))
    )
    (net (code "52") (name "Net-(DZ5F-C)") (class "Default")
      (node (ref "DZ5") (pin "14") (pinfunction "C_14") (pintype "passive"))
      (node (ref "RN6") (pin "4") (pinfunction "4_4") (pintype "passive"))
    )
    (net (code "53") (name "Net-(DZ5G-C)") (class "Default")
      (node (ref "DZ5") (pin "15") (pinfunction "C_15") (pintype "passive"))
      (node (ref "RN6") (pin "3") (pinfunction "3_3") (pintype "passive"))
    )
    (net (code "54") (name "Net-(DZ5H-C)") (class "Default")
      (node (ref "DZ5") (pin "16") (pinfunction "C_16") (pintype "passive"))
      (node (ref "RN6") (pin "2") (pinfunction "2_2") (pintype "passive"))
    )
    (net (code "55") (name "Net-(IC1A-X)") (class "Default")
      (node (ref "IC1") (pin "3") (pinfunction "X_3") (pintype "bidirectional"))
      (node (ref "R43") (pin "1") (pinfunction "1_1") (pintype "passive"))
    )
    (net (code "56") (name "Net-(IC2A-QH*)") (class "Default")
      (node (ref "IC2") (pin "9") (pinfunction "QH*_9") (pintype "tri_state"))
      (node (ref "IC6") (pin "14") (pinfunction "SER_14") (pintype "input"))
    )
    (net (code "57") (name "Net-(IC3-GND)") (class "Default")
      (node (ref "IC3") (pin "3") (pinfunction "GND_3") (pintype "power_in"))
      (node (ref "R16") (pin "1") (pinfunction "1_1") (pintype "passive"))
    )
    (net (code "58") (name "Net-(IC3-IN)") (class "Default")
      (node (ref "IC3") (pin "1") (pinfunction "IN_1") (pintype "input"))
      (node (ref "R1") (pin "1") (pinfunction "1_1") (pintype "passive"))
    )
    (net (code "59") (name "Net-(IC4A-X)") (class "Default")
      (node (ref "IC4") (pin "3") (pinfunction "X_3") (pintype "bidirectional"))
      (node (ref "R44") (pin "1") (pinfunction "1_1") (pintype "passive"))
    )
    (net (code "60") (name "Net-(IC5-GND)") (class "Default")
      (node (ref "IC5") (pin "3") (pinfunction "GND_3") (pintype "power_in"))
      (node (ref "R17") (pin "1") (pinfunction "1_1") (pintype "passive"))
      (node (ref "R20") (pin "1") (pinfunction "1_1") (pintype "passive"))
    )
    (net (code "61") (name "Net-(IC5-IN)") (class "Default")
      (node (ref "IC5") (pin "1") (pinfunction "IN_1") (pintype "input"))
      (node (ref "R2") (pin "1") (pinfunction "1_1") (pintype "passive"))
    )
    (net (code "62") (name "Net-(IC7-GND)") (class "Default")
      (node (ref "IC7") (pin "3") (pinfunction "GND_3") (pintype "power_in"))
      (node (ref "R18") (pin "1") (pinfunction "1_1") (pintype "passive"))
      (node (ref "R19") (pin "1") (pinfunction "1_1") (pintype "passive"))
    )
    (net (code "63") (name "Net-(IC7-IN)") (class "Default")
      (node (ref "IC7") (pin "1") (pinfunction "IN_1") (pintype "input"))
      (node (ref "R3") (pin "1") (pinfunction "1_1") (pintype "passive"))
    )
    (net (code "64") (name "Net-(IC11A--IN)") (class "Default")
      (node (ref "IC11") (pin "2") (pinfunction "-IN_2") (pintype "input"))
      (node (ref "R1_1") (pin "1") (pinfunction "1_1") (pintype "passive"))
      (node (ref "R1_2") (pin "2") (pinfunction "2_2") (pintype "passive"))
    )
    (net (code "65") (name "Net-(IC11B--IN)") (class "Default")
      (node (ref "IC11") (pin "6") (pinfunction "-IN_6") (pintype "input"))
      (node (ref "R2_1") (pin "1") (pinfunction "1_1") (pintype "passive"))
      (node (ref "R2_2") (pin "2") (pinfunction "2_2") (pintype "passive"))
    )
    (net (code "66") (name "Net-(L1-1)") (class "Default")
      (node (ref "D8") (pin "C") (pinfunction "C_C") (pintype "passive"))
      (node (ref "L1") (pin "P$1") (pinfunction "1_P$1") (pintype "passive"))
      (node (ref "U6") (pin "2") (pinfunction "SWE_2") (pintype "passive"))
    )
    (net (code "67") (name "Net-(LED1-PadBA)") (class "Default")
      (node (ref "LED1") (pin "BA") (pinfunction "BA_BA") (pintype "passive"))
      (node (ref "LED2") (pin "BC") (pinfunction "BC_BC") (pintype "passive"))
    )
    (net (code "68") (name "Net-(LED1-PadBC)") (class "Default")
      (node (ref "LED1") (pin "BC") (pinfunction "BC_BC") (pintype "passive"))
      (node (ref "R18") (pin "2") (pinfunction "2_2") (pintype "passive"))
    )
    (net (code "69") (name "Net-(LED1-PadGA)") (class "Default")
      (node (ref "LED1") (pin "GA") (pinfunction "GA_GA") (pintype "passive"))
      (node (ref "LED2") (pin "GC") (pinfunction "GC_GC") (pintype "passive"))
    )
    (net (code "70") (name "Net-(LED1-PadGC)") (class "Default")
      (node (ref "LED1") (pin "GC") (pinfunction "GC_GC") (pintype "passive"))
      (node (ref "R17") (pin "2") (pinfunction "2_2") (pintype "passive"))
    )
    (net (code "71") (name "Net-(LED1-PadRA)") (class "Default")
      (node (ref "LED1") (pin "RA") (pinfunction "RA_RA") (pintype "passive"))
      (node (ref "LED2") (pin "RC") (pinfunction "RC_RC") (pintype "passive"))
    )
    (net (code "72") (name "Net-(LED1-PadRC)") (class "Default")
      (node (ref "LED1") (pin "RC") (pinfunction "RC_RC") (pintype "passive"))
      (node (ref "R16") (pin "2") (pinfunction "2_2") (pintype "passive"))
    )
    (net (code "73") (name "Net-(LED2-PadBA)") (class "Default")
      (node (ref "LED2") (pin "BA") (pinfunction "BA_BA") (pintype "passive"))
      (node (ref "LED3") (pin "BC") (pinfunction "BC_BC") (pintype "passive"))
    )
    (net (code "74") (name "Net-(LED2-PadGA)") (class "Default")
      (node (ref "LED2") (pin "GA") (pinfunction "GA_GA") (pintype "passive"))
      (node (ref "LED3") (pin "GC") (pinfunction "GC_GC") (pintype "passive"))
    )
    (net (code "75") (name "Net-(LED2-PadRA)") (class "Default")
      (node (ref "LED2") (pin "RA") (pinfunction "RA_RA") (pintype "passive"))
      (node (ref "LED3") (pin "RC") (pinfunction "RC_RC") (pintype "passive"))
    )
    (net (code "76") (name "Net-(LED3-PadBA)") (class "Default")
      (node (ref "LED3") (pin "BA") (pinfunction "BA_BA") (pintype "passive"))
      (node (ref "LED4") (pin "BC") (pinfunction "BC_BC") (pintype "passive"))
    )
    (net (code "77") (name "Net-(LED3-PadGA)") (class "Default")
      (node (ref "LED3") (pin "GA") (pinfunction "GA_GA") (pintype "passive"))
      (node (ref "LED4") (pin "GC") (pinfunction "GC_GC") (pintype "passive"))
    )
    (net (code "78") (name "Net-(LED3-PadRA)") (class "Default")
      (node (ref "LED3") (pin "RA") (pinfunction "RA_RA") (pintype "passive"))
      (node (ref "LED4") (pin "RC") (pinfunction "RC_RC") (pintype "passive"))
    )
    (net (code "79") (name "Net-(LED4-PadBA)") (class "Default")
      (node (ref "LED4") (pin "BA") (pinfunction "BA_BA") (pintype "passive"))
      (node (ref "LED5") (pin "BC") (pinfunction "BC_BC") (pintype "passive"))
    )
    (net (code "80") (name "Net-(LED4-PadGA)") (class "Default")
      (node (ref "LED4") (pin "GA") (pinfunction "GA_GA") (pintype "passive"))
      (node (ref "LED5") (pin "GC") (pinfunction "GC_GC") (pintype "passive"))
    )
    (net (code "81") (name "Net-(LED4-PadRA)") (class "Default")
      (node (ref "LED4") (pin "RA") (pinfunction "RA_RA") (pintype "passive"))
      (node (ref "LED5") (pin "RC") (pinfunction "RC_RC") (pintype "passive"))
    )
    (net (code "82") (name "Net-(LED5-PadRA)") (class "Default")
      (node (ref "LED5") (pin "RA") (pinfunction "RA_RA") (pintype "passive"))
      (node (ref "LED6") (pin "RC") (pinfunction "RC_RC") (pintype "passive"))
    )
    (net (code "83") (name "Net-(LED6-PadBA)") (class "Default")
      (node (ref "LED6") (pin "BA") (pinfunction "BA_BA") (pintype "passive"))
      (node (ref "LED7") (pin "BC") (pinfunction "BC_BC") (pintype "passive"))
    )
    (net (code "84") (name "Net-(LED6-PadBC)") (class "Default")
      (node (ref "LED6") (pin "BC") (pinfunction "BC_BC") (pintype "passive"))
      (node (ref "R19") (pin "2") (pinfunction "2_2") (pintype "passive"))
    )
    (net (code "85") (name "Net-(LED6-PadGA)") (class "Default")
      (node (ref "LED6") (pin "GA") (pinfunction "GA_GA") (pintype "passive"))
      (node (ref "LED7") (pin "GC") (pinfunction "GC_GC") (pintype "passive"))
    )
    (net (code "86") (name "Net-(LED6-PadGC)") (class "Default")
      (node (ref "LED6") (pin "GC") (pinfunction "GC_GC") (pintype "passive"))
      (node (ref "R20") (pin "2") (pinfunction "2_2") (pintype "passive"))
    )
    (net (code "87") (name "Net-(LED6-PadRA)") (class "Default")
      (node (ref "LED6") (pin "RA") (pinfunction "RA_RA") (pintype "passive"))
      (node (ref "LED7") (pin "RC") (pinfunction "RC_RC") (pintype "passive"))
    )
    (net (code "88") (name "Net-(LED7-PadBA)") (class "Default")
      (node (ref "LED7") (pin "BA") (pinfunction "BA_BA") (pintype "passive"))
      (node (ref "LED8") (pin "BC") (pinfunction "BC_BC") (pintype "passive"))
    )
    (net (code "89") (name "Net-(LED7-PadGA)") (class "Default")
      (node (ref "LED7") (pin "GA") (pinfunction "GA_GA") (pintype "passive"))
      (node (ref "LED8") (pin "GC") (pinfunction "GC_GC") (pintype "passive"))
    )
    (net (code "90") (name "Net-(LED7-PadRA)") (class "Default")
      (node (ref "LED7") (pin "RA") (pinfunction "RA_RA") (pintype "passive"))
      (node (ref "LED8") (pin "RC") (pinfunction "RC_RC") (pintype "passive"))
    )
    (net (code "91") (name "Net-(LED8-PadBA)") (class "Default")
      (node (ref "LED8") (pin "BA") (pinfunction "BA_BA") (pintype "passive"))
      (node (ref "LED9") (pin "BC") (pinfunction "BC_BC") (pintype "passive"))
    )
    (net (code "92") (name "Net-(LED8-PadGA)") (class "Default")
      (node (ref "LED8") (pin "GA") (pinfunction "GA_GA") (pintype "passive"))
      (node (ref "LED9") (pin "GC") (pinfunction "GC_GC") (pintype "passive"))
    )
    (net (code "93") (name "Net-(LED8-PadRA)") (class "Default")
      (node (ref "LED8") (pin "RA") (pinfunction "RA_RA") (pintype "passive"))
      (node (ref "LED9") (pin "RC") (pinfunction "RC_RC") (pintype "passive"))
    )
    (net (code "94") (name "Net-(LED10-PadBC)") (class "Default")
      (node (ref "LED10") (pin "BC") (pinfunction "BC_BC") (pintype "passive"))
      (node (ref "LED9") (pin "BA") (pinfunction "BA_BA") (pintype "passive"))
    )
    (net (code "95") (name "Net-(LED10-PadGC)") (class "Default")
      (node (ref "LED10") (pin "GC") (pinfunction "GC_GC") (pintype "passive"))
      (node (ref "LED9") (pin "GA") (pinfunction "GA_GA") (pintype "passive"))
    )
    (net (code "96") (name "Net-(LED10-PadRC)") (class "Default")
      (node (ref "LED10") (pin "RC") (pinfunction "RC_RC") (pintype "passive"))
      (node (ref "LED9") (pin "RA") (pinfunction "RA_RA") (pintype "passive"))
    )
    (net (code "97") (name "Net-(SW1-1)") (class "Default")
      (node (ref "R37") (pin "1") (pinfunction "1_1") (pintype "passive"))
      (node (ref "SW1") (pin "P$1") (pinfunction "1_P$1") (pintype "bidirectional"))
    )
    (net (code "98") (name "Net-(U1-OSC_IN)") (class "Default")
      (node (ref "U1") (pin "5") (pinfunction "OSC_IN_5") (pintype "input"))
      (node (ref "X1") (pin "1") (pinfunction "1_1") (pintype "passive"))
    )
    (net (code "99") (name "Net-(U1-OSC_OUT)") (class "Default")
      (node (ref "U1") (pin "6") (pinfunction "OSC_OUT_6") (pintype "output"))
      (node (ref "X1") (pin "3") (pinfunction "3_3") (pintype "passive"))
    )
    (net (code "100") (name "Net-(U6-DC)") (class "Default")
      (node (ref "R40") (pin "2") (pinfunction "2_2") (pintype "passive"))
      (node (ref "U6") (pin "1") (pinfunction "SWC_1") (pintype "passive"))
      (node (ref "U6") (pin "7") (pinfunction "IS_7") (pintype "passive"))
      (node (ref "U6") (pin "8") (pinfunction "DC_8") (pintype "passive"))
    )
    (net (code "101") (name "Net-(U6-FB)") (class "Default")
      (node (ref "R41") (pin "1") (pinfunction "1_1") (pintype "passive"))
      (node (ref "R42") (pin "2") (pinfunction "2_2") (pintype "passive"))
      (node (ref "U6") (pin "5") (pinfunction "FB_5") (pintype "passive"))
    )
    (net (code "102") (name "Net-(U6-TC)") (class "Default")
      (node (ref "C17") (pin "1") (pinfunction "1_1") (pintype "passive"))
      (node (ref "U6") (pin "3") (pinfunction "TC_3") (pintype "passive"))
    )
    (net (code "103") (name "PD0") (class "Default")
      (node (ref "IC1") (pin "1") (pinfunction "X4_1") (pintype "bidirectional"))
      (node (ref "PD0") (pin "A") (pinfunction "A_A") (pintype "passive"))
      (node (ref "RN1") (pin "9") (pinfunction "9_9") (pintype "passive"))
    )
    (net (code "104") (name "PD1") (class "Default")
      (node (ref "IC1") (pin "2") (pinfunction "X6_2") (pintype "bidirectional"))
      (node (ref "PD1") (pin "A") (pinfunction "A_A") (pintype "passive"))
      (node (ref "RN1") (pin "8") (pinfunction "8_8") (pintype "passive"))
    )
    (net (code "105") (name "PD2") (class "Default")
      (node (ref "IC1") (pin "4") (pinfunction "X7_4") (pintype "bidirectional"))
      (node (ref "PD2") (pin "A") (pinfunction "A_A") (pintype "passive"))
      (node (ref "RN1") (pin "7") (pinfunction "7_7") (pintype "passive"))
    )
    (net (code "106") (name "PD3") (class "Default")
      (node (ref "IC1") (pin "5") (pinfunction "X5_5") (pintype "bidirectional"))
      (node (ref "PD3") (pin "A") (pinfunction "A_A") (pintype "passive"))
      (node (ref "RN1") (pin "6") (pinfunction "6_6") (pintype "passive"))
    )
    (net (code "107") (name "PD4") (class "Default")
      (node (ref "IC1") (pin "15") (pinfunction "X2_15") (pintype "bidirectional"))
      (node (ref "PD4") (pin "A") (pinfunction "A_A") (pintype "passive"))
      (node (ref "RN1") (pin "5") (pinfunction "5_5") (pintype "passive"))
    )
    (net (code "108") (name "PD5") (class "Default")
      (node (ref "IC1") (pin "14") (pinfunction "X1_14") (pintype "bidirectional"))
      (node (ref "PD5") (pin "A") (pinfunction "A_A") (pintype "passive"))
      (node (ref "RN1") (pin "4") (pinfunction "4_4") (pintype "passive"))
    )
    (net (code "109") (name "PD6") (class "Default")
      (node (ref "IC1") (pin "13") (pinfunction "X0_13") (pintype "bidirectional"))
      (node (ref "PD6") (pin "A") (pinfunction "A_A") (pintype "passive"))
      (node (ref "RN1") (pin "3") (pinfunction "3_3") (pintype "passive"))
    )
    (net (code "110") (name "PD7") (class "Default")
      (node (ref "IC1") (pin "12") (pinfunction "X3_12") (pintype "bidirectional"))
      (node (ref "PD7") (pin "A") (pinfunction "A_A") (pintype "passive"))
      (node (ref "RN1") (pin "2") (pinfunction "2_2") (pintype "passive"))
    )
    (net (code "111") (name "PD8") (class "Default")
      (node (ref "IC4") (pin "1") (pinfunction "X4_1") (pintype "bidirectional"))
      (node (ref "PD8") (pin "A") (pinfunction "A_A") (pintype "passive"))
      (node (ref "RN2") (pin "9") (pinfunction "9_9") (pintype "passive"))
    )
    (net (code "112") (name "PD9") (class "Default")
      (node (ref "IC4") (pin "2") (pinfunction "X6_2") (pintype "bidirectional"))
      (node (ref "PD9") (pin "A") (pinfunction "A_A") (pintype "passive"))
      (node (ref "RN2") (pin "8") (pinfunction "8_8") (pintype "passive"))
    )
    (net (code "113") (name "PD10") (class "Default")
      (node (ref "IC4") (pin "4") (pinfunction "X7_4") (pintype "bidirectional"))
      (node (ref "PD10") (pin "A") (pinfunction "A_A") (pintype "passive"))
      (node (ref "RN2") (pin "7") (pinfunction "7_7") (pintype "passive"))
    )
    (net (code "114") (name "PD11") (class "Default")
      (node (ref "IC4") (pin "5") (pinfunction "X5_5") (pintype "bidirectional"))
      (node (ref "PD11") (pin "A") (pinfunction "A_A") (pintype "passive"))
      (node (ref "RN2") (pin "6") (pinfunction "6_6") (pintype "passive"))
    )
    (net (code "115") (name "PD12") (class "Default")
      (node (ref "IC4") (pin "15") (pinfunction "X2_15") (pintype "bidirectional"))
      (node (ref "PD12") (pin "A") (pinfunction "A_A") (pintype "passive"))
      (node (ref "RN2") (pin "5") (pinfunction "5_5") (pintype "passive"))
    )
    (net (code "116") (name "PD13") (class "Default")
      (node (ref "IC4") (pin "14") (pinfunction "X1_14") (pintype "bidirectional"))
      (node (ref "PD13") (pin "A") (pinfunction "A_A") (pintype "passive"))
      (node (ref "RN2") (pin "4") (pinfunction "4_4") (pintype "passive"))
    )
    (net (code "117") (name "PD14") (class "Default")
      (node (ref "IC4") (pin "13") (pinfunction "X0_13") (pintype "bidirectional"))
      (node (ref "PD14") (pin "A") (pinfunction "A_A") (pintype "passive"))
      (node (ref "RN2") (pin "3") (pinfunction "3_3") (pintype "passive"))
    )
    (net (code "118") (name "PD15") (class "Default")
      (node (ref "IC4") (pin "12") (pinfunction "X3_12") (pintype "bidirectional"))
      (node (ref "PD15") (pin "A") (pinfunction "A_A") (pintype "passive"))
      (node (ref "RN2") (pin "2") (pinfunction "2_2") (pintype "passive"))
    )
    (net (code "119") (name "PD_A") (class "Default")
      (node (ref "IC11") (pin "1") (pinfunction "OUT_1") (pintype "output"))
      (node (ref "R1_2") (pin "1") (pinfunction "1_1") (pintype "passive"))
      (node (ref "U1") (pin "10") (pinfunction "PA0-WKUP_10") (pintype "bidirectional"))
    )
    (net (code "120") (name "PD_B") (class "Default")
      (node (ref "IC11") (pin "7") (pinfunction "OUT_7") (pintype "output"))
      (node (ref "R2_2") (pin "1") (pinfunction "1_1") (pintype "passive"))
      (node (ref "U1") (pin "11") (pinfunction "PA1_11") (pintype "bidirectional"))
    )
    (net (code "121") (name "PD_PREA") (class "Default")
      (node (ref "C24") (pin "1") (pinfunction "1_1") (pintype "passive"))
      (node (ref "IC11") (pin "3") (pinfunction "+IN_3") (pintype "input"))
      (node (ref "R43") (pin "2") (pinfunction "2_2") (pintype "passive"))
      (node (ref "U1") (pin "13") (pinfunction "PA3_13") (pintype "bidirectional"))
    )
    (net (code "122") (name "PD_PREB") (class "Default")
      (node (ref "C25") (pin "1") (pinfunction "1_1") (pintype "passive"))
      (node (ref "IC11") (pin "5") (pinfunction "+IN_5") (pintype "input"))
      (node (ref "R44") (pin "2") (pinfunction "2_2") (pintype "passive"))
      (node (ref "U1") (pin "14") (pinfunction "PA4_14") (pintype "bidirectional"))
    )
    (net (code "123") (name "PD_SIG1") (class "Default")
      (node (ref "IC1") (pin "11") (pinfunction "A_11") (pintype "input"))
      (node (ref "IC4") (pin "11") (pinfunction "A_11") (pintype "input"))
      (node (ref "U1") (pin "20") (pinfunction "PB2-BOOT1_20") (pintype "bidirectional"))
    )
    (net (code "124") (name "PD_SIG2") (class "Default")
      (node (ref "IC1") (pin "10") (pinfunction "B_10") (pintype "input"))
      (node (ref "IC4") (pin "10") (pinfunction "B_10") (pintype "input"))
      (node (ref "U1") (pin "19") (pinfunction "PB1_19") (pintype "bidirectional"))
    )
    (net (code "125") (name "PD_SIG3") (class "Default")
      (node (ref "IC1") (pin "9") (pinfunction "C_9") (pintype "input"))
      (node (ref "IC4") (pin "9") (pinfunction "C_9") (pintype "input"))
      (node (ref "U1") (pin "18") (pinfunction "PB0_18") (pintype "bidirectional"))
    )
    (net (code "126") (name "RCK") (class "Default")
      (node (ref "IC2") (pin "12") (pinfunction "RCK_12") (pintype "input"))
      (node (ref "IC6") (pin "12") (pinfunction "RCK_12") (pintype "input"))
      (node (ref "U1") (pin "38") (pinfunction "PA15-JTDI_38") (pintype "bidirectional"))
    )
    (net (code "127") (name "SCK") (class "Default")
      (node (ref "IC2") (pin "11") (pinfunction "SCK_11") (pintype "input"))
      (node (ref "IC6") (pin "11") (pinfunction "SCK_11") (pintype "input"))
      (node (ref "U1") (pin "40") (pinfunction "PB4-JNTRST_40") (pintype "bidirectional"))
    )
    (net (code "128") (name "SER") (class "Default")
      (node (ref "IC2") (pin "14") (pinfunction "SER_14") (pintype "input"))
      (node (ref "U1") (pin "41") (pinfunction "PB5_41") (pintype "bidirectional"))
    )
    (net (code "129") (name "SWCLK") (class "Default")
      (node (ref "SV2") (pin "9") (pinfunction "9_9") (pintype "passive"))
      (node (ref "U1") (pin "37") (pinfunction "PA14-JTCK-SWCLK_37") (pintype "bidirectional"))
    )
    (net (code "130") (name "SWDIO") (class "Default")
      (node (ref "SV2") (pin "8") (pinfunction "8_8") (pintype "passive"))
      (node (ref "U1") (pin "34") (pinfunction "PA13-JTMS-SWDIO_34") (pintype "bidirectional"))
    )
    (net (code "131") (name "UART_RX") (class "Default")
      (node (ref "SV2") (pin "3") (pinfunction "3_3") (pintype "passive"))
      (node (ref "U1") (pin "43") (pinfunction "PB7_43") (pintype "bidirectional"))
    )
    (net (code "132") (name "UART_TX") (class "Default")
      (node (ref "SV2") (pin "4") (pinfunction "4_4") (pintype "passive"))
      (node (ref "U1") (pin "42") (pinfunction "PB6_42") (pintype "bidirectional"))
    )
    (net (code "133") (name "unconnected-(IC6A-QH*-Pad9)") (class "Default")
      (node (ref "IC6") (pin "9") (pinfunction "QH*_9") (pintype "tri_state"))
    )
    (net (code "134") (name "unconnected-(IC10-VI-Pad2)") (class "Default")
      (node (ref "IC10") (pin "2") (pinfunction "VI_2") (pintype "input"))
    )
    (net (code "135") (name "unconnected-(U1-PA2-Pad12)") (class "Default")
      (node (ref "U1") (pin "12") (pinfunction "PA2_12") (pintype "bidirectional"))
    )
    (net (code "136") (name "unconnected-(U1-PA5-Pad15)") (class "Default")
      (node (ref "U1") (pin "15") (pinfunction "PA5_15") (pintype "bidirectional"))
    )
    (net (code "137") (name "unconnected-(U1-PA6-Pad16)") (class "Default")
      (node (ref "U1") (pin "16") (pinfunction "PA6_16") (pintype "bidirectional"))
    )
    (net (code "138") (name "unconnected-(U1-PA7-Pad17)") (class "Default")
      (node (ref "U1") (pin "17") (pinfunction "PA7_17") (pintype "bidirectional"))
    )
    (net (code "139") (name "unconnected-(U1-PA8-Pad29)") (class "Default")
      (node (ref "U1") (pin "29") (pinfunction "PA8_29") (pintype "bidirectional"))
    )
    (net (code "140") (name "unconnected-(U1-PA9-Pad30)") (class "Default")
      (node (ref "U1") (pin "30") (pinfunction "PA9_30") (pintype "bidirectional"))
    )
    (net (code "141") (name "unconnected-(U1-PB10-Pad21)") (class "Default")
      (node (ref "U1") (pin "21") (pinfunction "PB10_21") (pintype "bidirectional"))
    )
    (net (code "142") (name "unconnected-(U1-PB11-Pad22)") (class "Default")
      (node (ref "U1") (pin "22") (pinfunction "PB11_22") (pintype "bidirectional"))
    )
    (net (code "143") (name "unconnected-(U1-PB14-Pad27)") (class "Default")
      (node (ref "U1") (pin "27") (pinfunction "PB14_27") (pintype "bidirectional"))
    )
    (net (code "144") (name "unconnected-(U1-PB15-Pad28)") (class "Default")
      (node (ref "U1") (pin "28") (pinfunction "PB15_28") (pintype "bidirectional"))
    )
    (net (code "145") (name "unconnected-(U1-PC15-OSC32_OUT-Pad4)") (class "Default")
      (node (ref "U1") (pin "4") (pinfunction "PC15-OSC32_OUT_4") (pintype "bidirectional"))
    )
    (net (code "146") (name "~{EMS}") (class "Default")
      (node (ref "R34") (pin "1") (pinfunction "1_1") (pintype "passive"))
      (node (ref "U1") (pin "26") (pinfunction "PB13_26") (pintype "bidirectional"))
    )
    (net (code "147") (name "~{RESET}") (class "Default")
      (node (ref "C20") (pin "2") (pinfunction "2_2") (pintype "passive"))
      (node (ref "GND") (pin "2") (pinfunction "2_2") (pintype "passive"))
      (node (ref "SW1") (pin "P$2") (pinfunction "2_P$2") (pintype "bidirectional"))
      (node (ref "U1") (pin "7") (pinfunction "NRST_7") (pintype "bidirectional"))
    )
    (net (code "148") (name "~{SCL}") (class "Default")
      (node (ref "IC2") (pin "10") (pinfunction "SCL_10") (pintype "input"))
      (node (ref "IC6") (pin "10") (pinfunction "SCL_10") (pintype "input"))
      (node (ref "U1") (pin "39") (pinfunction "PB3-JTDO_39") (pintype "bidirectional"))
    )
  )
)
